# Copy_of_KNX_Relay_16CH_V0_2.net
KiCad netlist of a schematic drawn in Altium Designer
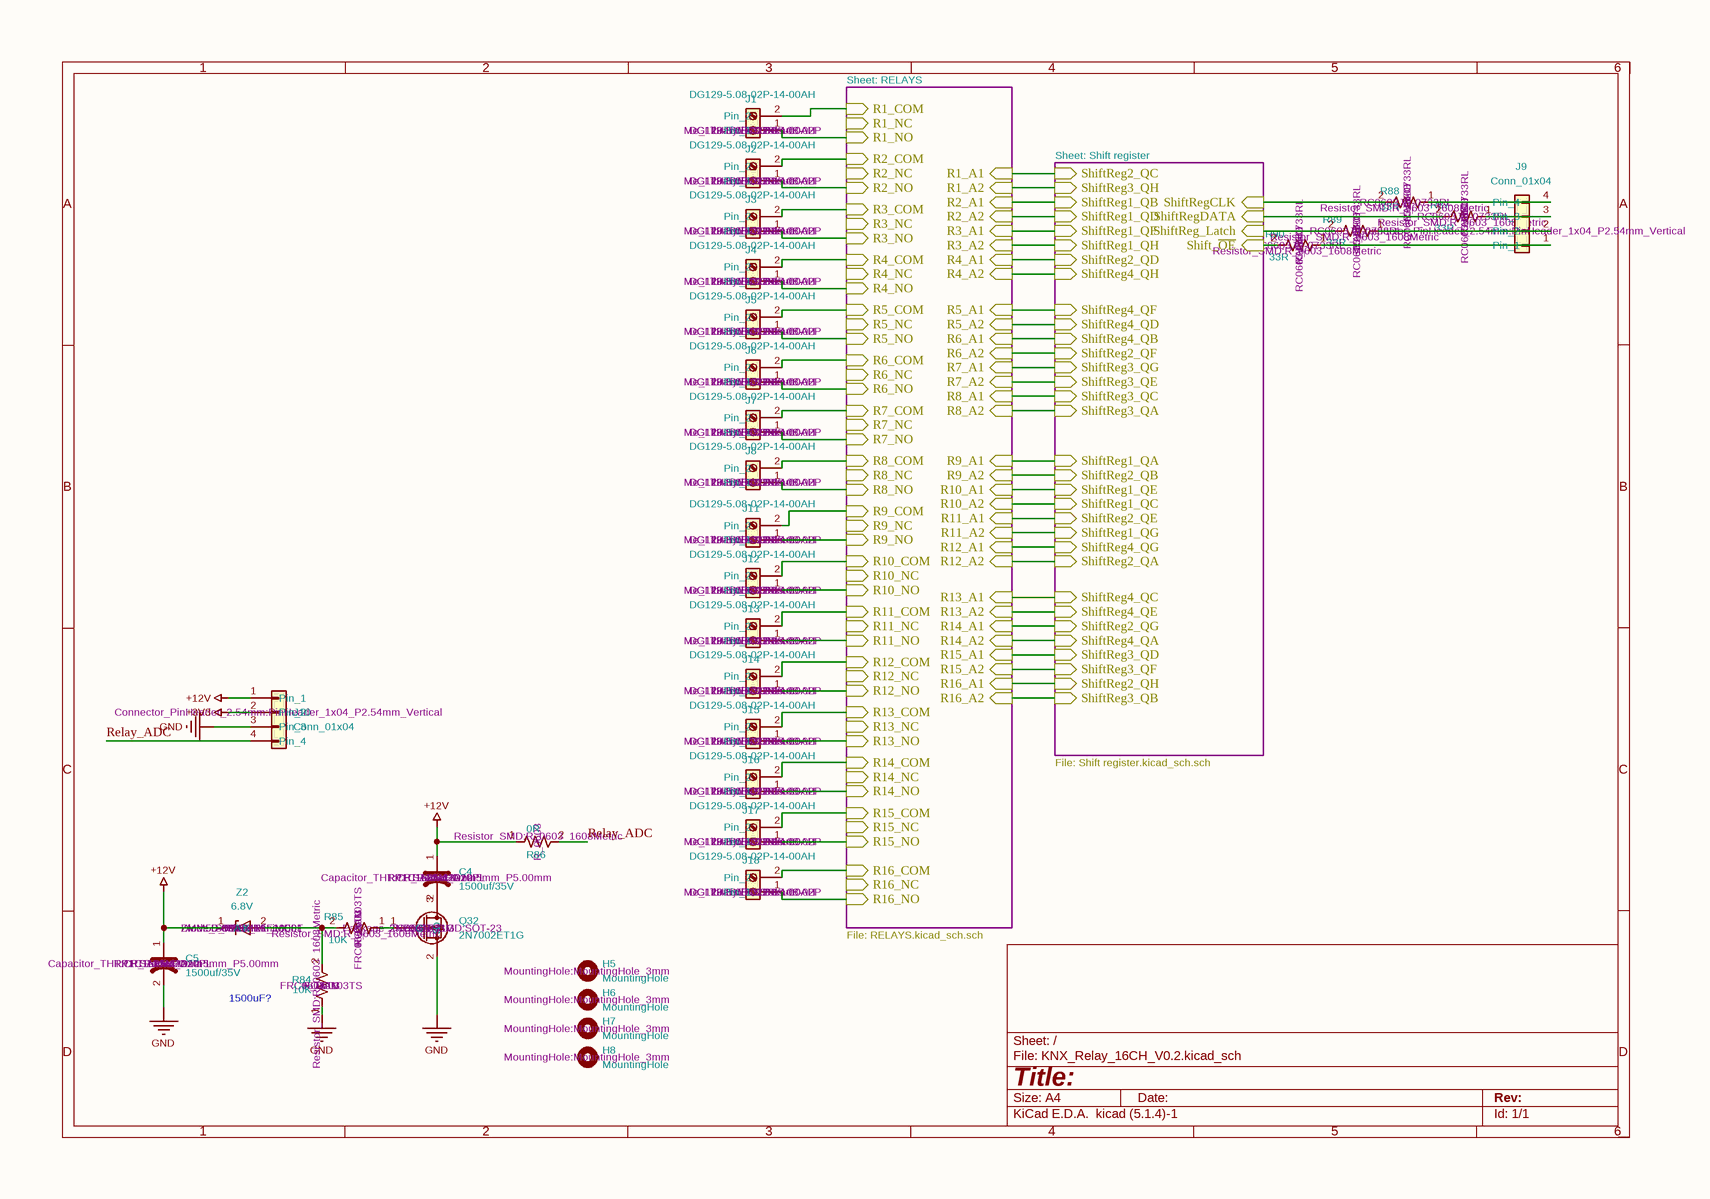
[diagram p0: Copy of KNX_Relay_16CH_V0.2.SchDoc]

(export (version "E")
  (design (tool "Eeschema 10.0.6"))
  (components
    (comp (ref "C4")
      (value "1500uf/35V")
      (footprint "Capacitor_THT:CP_Radial_D12.5mm_P5.00mm")
      (fields
        (field (name "MP") "RP1C158M12020PL")
        (field (name "MF") "SAMWHA")
        (field (name "PACKAGE") "THT 12.5x20mm")
        (field (name "OZD") "RP1C158M12020PL")
      )
      (libsource (lib "Device") (part "C_US"))
    )
    (comp (ref "C5")
      (value "1500uf/35V")
      (footprint "Capacitor_THT:CP_Radial_D12.5mm_P5.00mm")
      (fields
        (field (name "MP") "RP1C158M12020PL")
        (field (name "MF") "SAMWHA")
        (field (name "PACKAGE") "THT 12.5x20mm")
        (field (name "OZD") "RP1C158M12020PL")
      )
      (libsource (lib "Device") (part "C_US"))
    )
    (comp (ref "H5")
      (value "MountingHole")
      (footprint "MountingHole:MountingHole_3mm")
      (libsource (lib "Mechanical") (part "MountingHole"))
    )
    (comp (ref "H6")
      (value "MountingHole")
      (footprint "MountingHole:MountingHole_3mm")
      (libsource (lib "Mechanical") (part "MountingHole"))
    )
    (comp (ref "H7")
      (value "MountingHole")
      (footprint "MountingHole:MountingHole_3mm")
      (libsource (lib "Mechanical") (part "MountingHole"))
    )
    (comp (ref "H8")
      (value "MountingHole")
      (footprint "MountingHole:MountingHole_3mm")
      (libsource (lib "Mechanical") (part "MountingHole"))
    )
    (comp (ref "J1")
      (value "DG129-5.08-02P-14-00AH")
      (footprint "Me_Library:DG129-5.08-02P")
      (fields
        (field (name "MP") "DG129-5.08-02P-14-00AH")
        (field (name "MF") "DEGSON")
        (field (name "PACKAGE") "THT V/T  5.08mm")
        (field (name "OZD") "DG129-5.08-02P-14-00AH")
      )
      (libsource (lib "Connector") (part "Screw_Terminal_01x02"))
    )
    (comp (ref "J2")
      (value "DG129-5.08-02P-14-00AH")
      (footprint "Me_Library:DG129-5.08-02P")
      (fields
        (field (name "MP") "DG129-5.08-02P-14-00AH")
        (field (name "MF") "DEGSON")
        (field (name "PACKAGE") "THT V/T  5.08mm")
        (field (name "OZD") "DG129-5.08-02P-14-00AH")
      )
      (libsource (lib "Connector") (part "Screw_Terminal_01x02"))
    )
    (comp (ref "J3")
      (value "DG129-5.08-02P-14-00AH")
      (footprint "Me_Library:DG129-5.08-02P")
      (fields
        (field (name "MP") "DG129-5.08-02P-14-00AH")
        (field (name "MF") "DEGSON")
        (field (name "PACKAGE") "THT V/T  5.08mm")
        (field (name "OZD") "DG129-5.08-02P-14-00AH")
      )
      (libsource (lib "Connector") (part "Screw_Terminal_01x02"))
    )
    (comp (ref "J4")
      (value "DG129-5.08-02P-14-00AH")
      (footprint "Me_Library:DG129-5.08-02P")
      (fields
        (field (name "MP") "DG129-5.08-02P-14-00AH")
        (field (name "MF") "DEGSON")
        (field (name "PACKAGE") "THT V/T  5.08mm")
        (field (name "OZD") "DG129-5.08-02P-14-00AH")
      )
      (libsource (lib "Connector") (part "Screw_Terminal_01x02"))
    )
    (comp (ref "J5")
      (value "DG129-5.08-02P-14-00AH")
      (footprint "Me_Library:DG129-5.08-02P")
      (fields
        (field (name "MP") "DG129-5.08-02P-14-00AH")
        (field (name "MF") "DEGSON")
        (field (name "PACKAGE") "THT V/T  5.08mm")
        (field (name "OZD") "DG129-5.08-02P-14-00AH")
      )
      (libsource (lib "Connector") (part "Screw_Terminal_01x02"))
    )
    (comp (ref "J6")
      (value "DG129-5.08-02P-14-00AH")
      (footprint "Me_Library:DG129-5.08-02P")
      (fields
        (field (name "MP") "DG129-5.08-02P-14-00AH")
        (field (name "MF") "DEGSON")
        (field (name "PACKAGE") "THT V/T  5.08mm")
        (field (name "OZD") "DG129-5.08-02P-14-00AH")
      )
      (libsource (lib "Connector") (part "Screw_Terminal_01x02"))
    )
    (comp (ref "J7")
      (value "DG129-5.08-02P-14-00AH")
      (footprint "Me_Library:DG129-5.08-02P")
      (fields
        (field (name "MP") "DG129-5.08-02P-14-00AH")
        (field (name "MF") "DEGSON")
        (field (name "PACKAGE") "THT V/T  5.08mm")
        (field (name "OZD") "DG129-5.08-02P-14-00AH")
      )
      (libsource (lib "Connector") (part "Screw_Terminal_01x02"))
    )
    (comp (ref "J8")
      (value "DG129-5.08-02P-14-00AH")
      (footprint "Me_Library:DG129-5.08-02P")
      (fields
        (field (name "MP") "DG129-5.08-02P-14-00AH")
        (field (name "MF") "DEGSON")
        (field (name "PACKAGE") "THT V/T  5.08mm")
        (field (name "OZD") "DG129-5.08-02P-14-00AH")
      )
      (libsource (lib "Connector") (part "Screw_Terminal_01x02"))
    )
    (comp (ref "J9")
      (value "Conn_01x04")
      (footprint "Connector_PinHeader_2.54mm:PinHeader_1x04_P2.54mm_Vertical")
      (libsource (lib "Connector_Generic") (part "Conn_01x04"))
    )
    (comp (ref "J10")
      (value "Conn_01x04")
      (footprint "Connector_PinHeader_2.54mm:PinHeader_1x04_P2.54mm_Vertical")
      (libsource (lib "") (part "Conn_01x04_1"))
    )
    (comp (ref "J11")
      (value "DG129-5.08-02P-14-00AH")
      (footprint "Me_Library:DG129-5.08-02P")
      (fields
        (field (name "MP") "DG129-5.08-02P-14-00AH")
        (field (name "MF") "DEGSON")
        (field (name "PACKAGE") "THT V/T  5.08mm")
        (field (name "OZD") "DG129-5.08-02P-14-00AH")
      )
      (libsource (lib "Connector") (part "Screw_Terminal_01x02"))
    )
    (comp (ref "J12")
      (value "DG129-5.08-02P-14-00AH")
      (footprint "Me_Library:DG129-5.08-02P")
      (fields
        (field (name "MP") "DG129-5.08-02P-14-00AH")
        (field (name "MF") "DEGSON")
        (field (name "PACKAGE") "THT V/T  5.08mm")
        (field (name "OZD") "DG129-5.08-02P-14-00AH")
      )
      (libsource (lib "Connector") (part "Screw_Terminal_01x02"))
    )
    (comp (ref "J13")
      (value "DG129-5.08-02P-14-00AH")
      (footprint "Me_Library:DG129-5.08-02P")
      (fields
        (field (name "MP") "DG129-5.08-02P-14-00AH")
        (field (name "MF") "DEGSON")
        (field (name "PACKAGE") "THT V/T  5.08mm")
        (field (name "OZD") "DG129-5.08-02P-14-00AH")
      )
      (libsource (lib "Connector") (part "Screw_Terminal_01x02"))
    )
    (comp (ref "J14")
      (value "DG129-5.08-02P-14-00AH")
      (footprint "Me_Library:DG129-5.08-02P")
      (fields
        (field (name "MP") "DG129-5.08-02P-14-00AH")
        (field (name "MF") "DEGSON")
        (field (name "PACKAGE") "THT V/T  5.08mm")
        (field (name "OZD") "DG129-5.08-02P-14-00AH")
      )
      (libsource (lib "Connector") (part "Screw_Terminal_01x02"))
    )
    (comp (ref "J15")
      (value "DG129-5.08-02P-14-00AH")
      (footprint "Me_Library:DG129-5.08-02P")
      (fields
        (field (name "MP") "DG129-5.08-02P-14-00AH")
        (field (name "MF") "DEGSON")
        (field (name "PACKAGE") "THT V/T  5.08mm")
        (field (name "OZD") "DG129-5.08-02P-14-00AH")
      )
      (libsource (lib "Connector") (part "Screw_Terminal_01x02"))
    )
    (comp (ref "J16")
      (value "DG129-5.08-02P-14-00AH")
      (footprint "Me_Library:DG129-5.08-02P")
      (fields
        (field (name "MP") "DG129-5.08-02P-14-00AH")
        (field (name "MF") "DEGSON")
        (field (name "PACKAGE") "THT V/T  5.08mm")
        (field (name "OZD") "DG129-5.08-02P-14-00AH")
      )
      (libsource (lib "Connector") (part "Screw_Terminal_01x02"))
    )
    (comp (ref "J17")
      (value "DG129-5.08-02P-14-00AH")
      (footprint "Me_Library:DG129-5.08-02P")
      (fields
        (field (name "MP") "DG129-5.08-02P-14-00AH")
        (field (name "MF") "DEGSON")
        (field (name "PACKAGE") "THT V/T  5.08mm")
        (field (name "OZD") "DG129-5.08-02P-14-00AH")
      )
      (libsource (lib "Connector") (part "Screw_Terminal_01x02"))
    )
    (comp (ref "J18")
      (value "DG129-5.08-02P-14-00AH")
      (footprint "Me_Library:DG129-5.08-02P")
      (fields
        (field (name "MP") "DG129-5.08-02P-14-00AH")
        (field (name "MF") "DEGSON")
        (field (name "PACKAGE") "THT V/T  5.08mm")
        (field (name "OZD") "DG129-5.08-02P-14-00AH")
      )
      (libsource (lib "Connector") (part "Screw_Terminal_01x02"))
    )
    (comp (ref "Q32")
      (value "2N7002ET1G")
      (footprint "Package_TO_SOT_SMD:SOT-23")
      (fields
        (field (name "MP") "2N7002ET1G")
        (field (name "MF") "onsemi")
        (field (name "PACKAGE") "SOT-23")
        (field (name "OZD") "2N7002ET1G")
      )
      (libsource (lib "Transistor_FET_Other") (part "Q_NMOS_Depletion_GSD"))
    )
    (comp (ref "R84")
      (value "10K")
      (footprint "Resistor_SMD:R_0603_1608Metric")
      (fields
        (field (name "MP") "FRC0603J103TS")
        (field (name "MF") "FOJAN")
        (field (name "PACKAGE") "R_0603")
      )
      (libsource (lib "Device") (part "R_US"))
    )
    (comp (ref "R85")
      (value "10K")
      (footprint "Resistor_SMD:R_0603_1608Metric")
      (fields
        (field (name "MP") "FRC0603J103TS")
        (field (name "MF") "FOJAN")
        (field (name "PACKAGE") "R_0603")
      )
      (libsource (lib "Device") (part "R_US"))
    )
    (comp (ref "R86")
      (value "0R")
      (footprint "Resistor_SMD:R_0603_1608Metric")
      (fields (field (name "PACKAGE") "R_0603"))
      (libsource (lib "Device") (part "R_US"))
    )
    (comp (ref "R87")
      (value "33R")
      (footprint "Resistor_SMD:R_0603_1608Metric")
      (fields
        (field (name "MP") "RC0603JR-0733RL")
        (field (name "MF") "YAGEO")
        (field (name "PACKAGE") "R_0603")
        (field (name "OZD") "RC0603JR-0733RL")
      )
      (libsource (lib "Device") (part "R_US"))
    )
    (comp (ref "R88")
      (value "33R")
      (footprint "Resistor_SMD:R_0603_1608Metric")
      (fields
        (field (name "MP") "RC0603JR-0733RL")
        (field (name "MF") "YAGEO")
        (field (name "PACKAGE") "R_0603")
        (field (name "OZD") "RC0603JR-0733RL")
      )
      (libsource (lib "Device") (part "R_US"))
    )
    (comp (ref "R89")
      (value "33R")
      (footprint "Resistor_SMD:R_0603_1608Metric")
      (fields
        (field (name "MP") "RC0603JR-0733RL")
        (field (name "MF") "YAGEO")
        (field (name "PACKAGE") "R_0603")
        (field (name "OZD") "RC0603JR-0733RL")
      )
      (libsource (lib "Device") (part "R_US"))
    )
    (comp (ref "R90")
      (value "33R")
      (footprint "Resistor_SMD:R_0603_1608Metric")
      (fields
        (field (name "MP") "RC0603JR-0733RL")
        (field (name "MF") "YAGEO")
        (field (name "PACKAGE") "R_0603")
        (field (name "OZD") "RC0603JR-0733RL")
      )
      (libsource (lib "Device") (part "R_US"))
    )
    (comp (ref "Z2")
      (value "6.8V")
      (footprint "Diode_SMD:D_MiniMELF")
      (fields
        (field (name "MF") "PANJIT")
        (field (name "MP") "ZMM55-C6V8_R1_10001")
        (field (name "OZD") "ZMM55-C6V8_R1_10001")
        (field (name "PACKAGE") "D_MiniMELF")
      )
      (libsource (lib "Device") (part "D_Zener"))
    )
  )
  (nets
    (net (code "1") (name "+3V3") (class "Default")
      (node (ref "J10") (pin "2") (pinfunction "Pin_2_2") (pintype "passive"))
    )
    (net (code "2") (name "+12V") (class "Default")
      (node (ref "C4") (pin "1") (pinfunction "1_1") (pintype "passive"))
      (node (ref "C5") (pin "1") (pinfunction "1_1") (pintype "passive"))
      (node (ref "J10") (pin "1") (pinfunction "Pin_1_1") (pintype "passive"))
      (node (ref "R86") (pin "1") (pinfunction "1_1") (pintype "passive"))
      (node (ref "Z2") (pin "1") (pinfunction "K_1") (pintype "passive"))
    )
    (net (code "5") (name "/R1_COM") (class "Default")
      (node (ref "J1") (pin "2") (pinfunction "Pin_2_2") (pintype "passive"))
    )
    (net (code "7") (name "/R1_NO") (class "Default")
      (node (ref "J1") (pin "1") (pinfunction "Pin_1_1") (pintype "passive"))
    )
    (net (code "10") (name "/R2_COM") (class "Default")
      (node (ref "J2") (pin "2") (pinfunction "Pin_2_2") (pintype "passive"))
    )
    (net (code "12") (name "/R2_NO") (class "Default")
      (node (ref "J2") (pin "1") (pinfunction "Pin_1_1") (pintype "passive"))
    )
    (net (code "15") (name "/R3_COM") (class "Default")
      (node (ref "J3") (pin "2") (pinfunction "Pin_2_2") (pintype "passive"))
    )
    (net (code "17") (name "/R3_NO") (class "Default")
      (node (ref "J3") (pin "1") (pinfunction "Pin_1_1") (pintype "passive"))
    )
    (net (code "20") (name "/R4_COM") (class "Default")
      (node (ref "J4") (pin "2") (pinfunction "Pin_2_2") (pintype "passive"))
    )
    (net (code "22") (name "/R4_NO") (class "Default")
      (node (ref "J4") (pin "1") (pinfunction "Pin_1_1") (pintype "passive"))
    )
    (net (code "25") (name "/R5_COM") (class "Default")
      (node (ref "J5") (pin "2") (pinfunction "Pin_2_2") (pintype "passive"))
    )
    (net (code "27") (name "/R5_NO") (class "Default")
      (node (ref "J5") (pin "1") (pinfunction "Pin_1_1") (pintype "passive"))
    )
    (net (code "30") (name "/R6_COM") (class "Default")
      (node (ref "J6") (pin "2") (pinfunction "Pin_2_2") (pintype "passive"))
    )
    (net (code "32") (name "/R6_NO") (class "Default")
      (node (ref "J6") (pin "1") (pinfunction "Pin_1_1") (pintype "passive"))
    )
    (net (code "35") (name "/R7_COM") (class "Default")
      (node (ref "J7") (pin "2") (pinfunction "Pin_2_2") (pintype "passive"))
    )
    (net (code "37") (name "/R7_NO") (class "Default")
      (node (ref "J7") (pin "1") (pinfunction "Pin_1_1") (pintype "passive"))
    )
    (net (code "40") (name "/R8_COM") (class "Default")
      (node (ref "J8") (pin "2") (pinfunction "Pin_2_2") (pintype "passive"))
    )
    (net (code "42") (name "/R8_NO") (class "Default")
      (node (ref "J8") (pin "1") (pinfunction "Pin_1_1") (pintype "passive"))
    )
    (net (code "45") (name "/R9_COM") (class "Default")
      (node (ref "J11") (pin "2") (pinfunction "Pin_2_2") (pintype "passive"))
    )
    (net (code "47") (name "/R9_NO") (class "Default")
      (node (ref "J11") (pin "1") (pinfunction "Pin_1_1") (pintype "passive"))
    )
    (net (code "50") (name "/R10_COM") (class "Default")
      (node (ref "J12") (pin "2") (pinfunction "Pin_2_2") (pintype "passive"))
    )
    (net (code "52") (name "/R10_NO") (class "Default")
      (node (ref "J12") (pin "1") (pinfunction "Pin_1_1") (pintype "passive"))
    )
    (net (code "55") (name "/R11_COM") (class "Default")
      (node (ref "J13") (pin "2") (pinfunction "Pin_2_2") (pintype "passive"))
    )
    (net (code "57") (name "/R11_NO") (class "Default")
      (node (ref "J13") (pin "1") (pinfunction "Pin_1_1") (pintype "passive"))
    )
    (net (code "60") (name "/R12_COM") (class "Default")
      (node (ref "J14") (pin "2") (pinfunction "Pin_2_2") (pintype "passive"))
    )
    (net (code "62") (name "/R12_NO") (class "Default")
      (node (ref "J14") (pin "1") (pinfunction "Pin_1_1") (pintype "passive"))
    )
    (net (code "65") (name "/R13_COM") (class "Default")
      (node (ref "J15") (pin "2") (pinfunction "Pin_2_2") (pintype "passive"))
    )
    (net (code "67") (name "/R13_NO") (class "Default")
      (node (ref "J15") (pin "1") (pinfunction "Pin_1_1") (pintype "passive"))
    )
    (net (code "70") (name "/R14_COM") (class "Default")
      (node (ref "J16") (pin "2") (pinfunction "Pin_2_2") (pintype "passive"))
    )
    (net (code "72") (name "/R14_NO") (class "Default")
      (node (ref "J16") (pin "1") (pinfunction "Pin_1_1") (pintype "passive"))
    )
    (net (code "75") (name "/R15_COM") (class "Default")
      (node (ref "J17") (pin "2") (pinfunction "Pin_2_2") (pintype "passive"))
    )
    (net (code "77") (name "/R15_NO") (class "Default")
      (node (ref "J17") (pin "1") (pinfunction "Pin_1_1") (pintype "passive"))
    )
    (net (code "80") (name "/R16_COM") (class "Default")
      (node (ref "J18") (pin "2") (pinfunction "Pin_2_2") (pintype "passive"))
    )
    (net (code "82") (name "/R16_NO") (class "Default")
      (node (ref "J18") (pin "1") (pinfunction "Pin_1_1") (pintype "passive"))
    )
    (net (code "83") (name "/Relay_ADC") (class "Default")
      (node (ref "J10") (pin "4") (pinfunction "Pin_4_4") (pintype "passive"))
      (node (ref "R86") (pin "2") (pinfunction "2_2") (pintype "passive"))
    )
    (net (code "84") (name "/ShiftRegCLK") (class "Default")
      (node (ref "R88") (pin "2") (pinfunction "2_2") (pintype "passive"))
    )
    (net (code "85") (name "/ShiftRegDATA") (class "Default")
      (node (ref "R87") (pin "2") (pinfunction "2_2") (pintype "passive"))
    )
    (net (code "86") (name "/ShiftReg_Latch") (class "Default")
      (node (ref "R89") (pin "2") (pinfunction "2_2") (pintype "passive"))
    )
    (net (code "87") (name "/Shift_~{OE}") (class "Default")
      (node (ref "R90") (pin "2") (pinfunction "2_2") (pintype "passive"))
    )
    (net (code "88") (name "GND") (class "Default")
      (node (ref "C5") (pin "2") (pinfunction "2_2") (pintype "passive"))
      (node (ref "J10") (pin "3") (pinfunction "Pin_3_3") (pintype "passive"))
      (node (ref "Q32") (pin "2") (pinfunction "S_2") (pintype "passive"))
      (node (ref "R84") (pin "1") (pinfunction "1_1") (pintype "passive"))
    )
    (net (code "89") (name "Net-(J9-Pin_1)") (class "Default")
      (node (ref "J9") (pin "1") (pinfunction "Pin_1_1") (pintype "passive"))
      (node (ref "R90") (pin "1") (pinfunction "1_1") (pintype "passive"))
    )
    (net (code "90") (name "Net-(J9-Pin_2)") (class "Default")
      (node (ref "J9") (pin "2") (pinfunction "Pin_2_2") (pintype "passive"))
      (node (ref "R89") (pin "1") (pinfunction "1_1") (pintype "passive"))
    )
    (net (code "91") (name "Net-(J9-Pin_3)") (class "Default")
      (node (ref "J9") (pin "3") (pinfunction "Pin_3_3") (pintype "passive"))
      (node (ref "R87") (pin "1") (pinfunction "1_1") (pintype "passive"))
    )
    (net (code "92") (name "Net-(J9-Pin_4)") (class "Default")
      (node (ref "J9") (pin "4") (pinfunction "Pin_4_4") (pintype "passive"))
      (node (ref "R88") (pin "1") (pinfunction "1_1") (pintype "passive"))
    )
    (net (code "93") (name "Net-(Q32-D)") (class "Default")
      (node (ref "C4") (pin "2") (pinfunction "2_2") (pintype "passive"))
      (node (ref "Q32") (pin "3") (pinfunction "D_3") (pintype "passive"))
    )
    (net (code "94") (name "Net-(Q32-G)") (class "Default")
      (node (ref "Q32") (pin "1") (pinfunction "G_1") (pintype "passive"))
      (node (ref "R85") (pin "1") (pinfunction "1_1") (pintype "passive"))
    )
    (net (code "95") (name "Net-(Z2-A)") (class "Default")
      (node (ref "R84") (pin "2") (pinfunction "2_2") (pintype "passive"))
      (node (ref "R85") (pin "2") (pinfunction "2_2") (pintype "passive"))
      (node (ref "Z2") (pin "2") (pinfunction "A_2") (pintype "passive"))
    )
  )
)
